# Schemat.net
KiCad netlist of a schematic drawn in Altium Designer
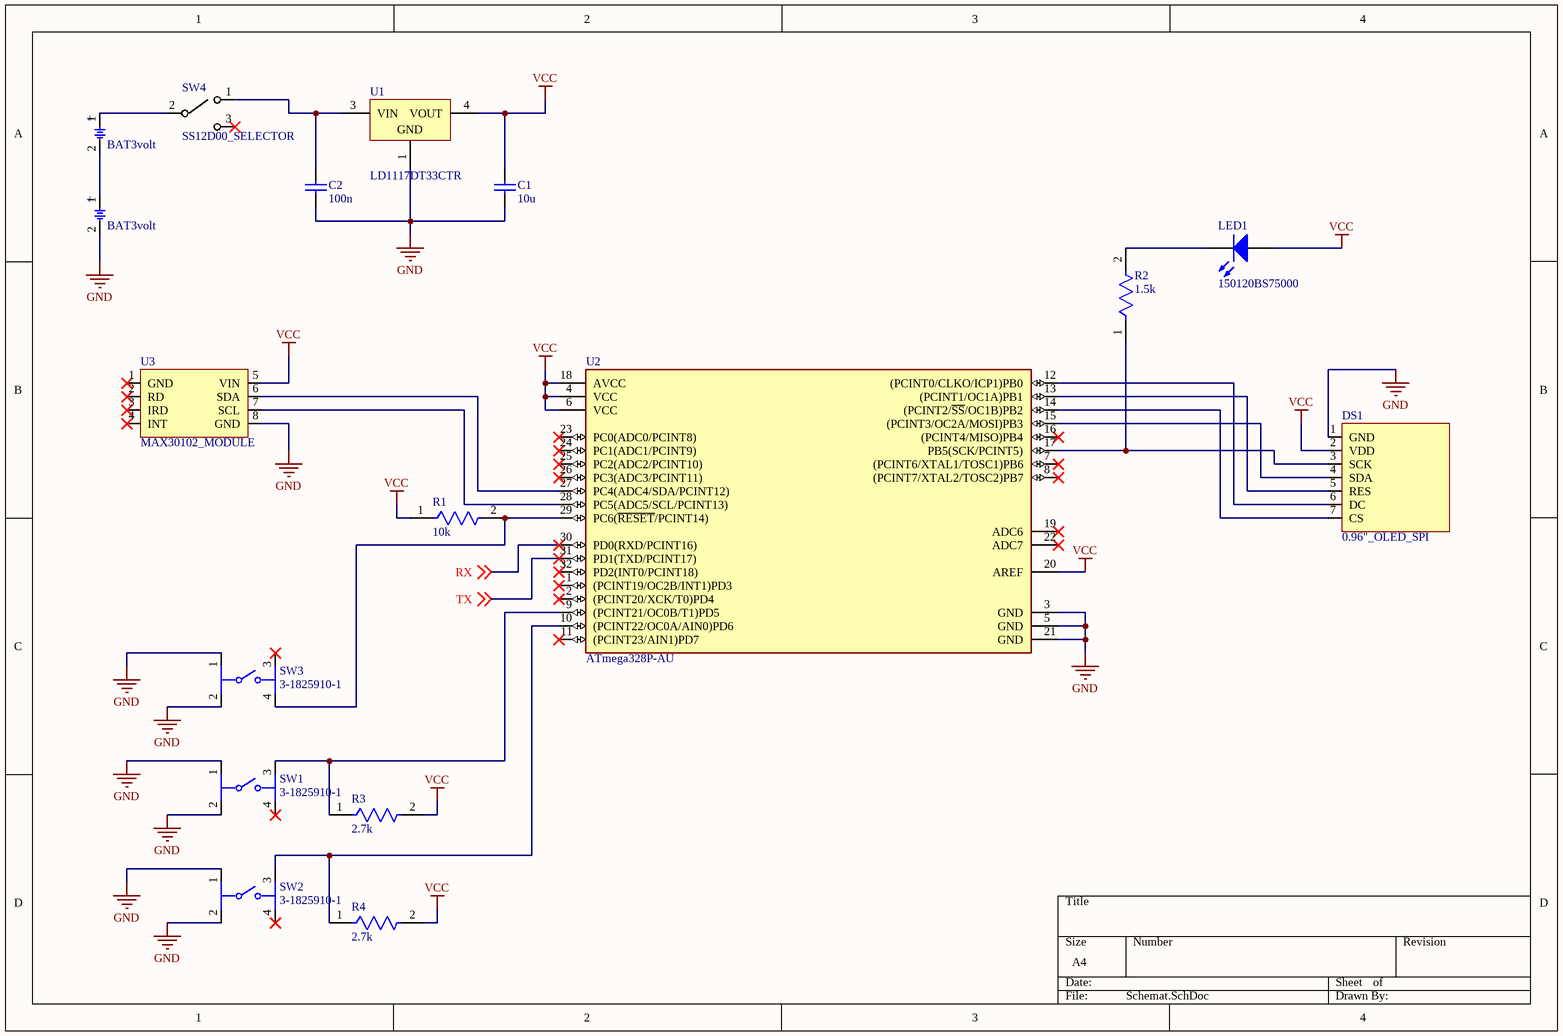
[diagram p0: Schemat.SchDoc]

(export (version "E")
  (design (tool "Eeschema 10.0.6"))
  (components
    (comp (ref "BT1")
      (value "BAT3volt")
      (footprint "BTH2032")
      (description "BATTERY HOLDER, CR2032")
      (libsource (lib "BTH2032") (part "BATH_CR2032"))
    )
    (comp (ref "BT2")
      (value "BAT3volt")
      (footprint "BTH2032")
      (description "BATTERY HOLDER, CR2032")
      (libsource (lib "BTH2032") (part "BATH_CR2032"))
    )
    (comp (ref "C1")
      (value "10u")
      (footprint "CAPC3216X180X50LL20T25")
      (description "Chip Capacitor, 10 uF, +/- 10%, 10 V, -55 to 125 degC, 1206 (3216 Metric), RoHS, Tape and Reel")
      (fields (field (name "TOLERANCE") "10%") (field (name "MANUFACTURER") "Kemet"))
      (libsource (lib "Altium Content Vault") (part "CAP-NP-2"))
    )
    (comp (ref "C2")
      (value "100n")
      (footprint "CAPC3216X94X50ML20T25")
      (description "Chip Capacitor, Ceramic, 100 nF, 10%, 50 V, 1206, RoHS, Tape and Reel")
      (fields (field (name "MANUFACTURER") "AVX"))
      (libsource (lib "Altium Content Vault") (part "CAP-NP-2"))
    )
    (comp (ref "DS1")
      (value "0.96\"_OLED_SPI")
      (footprint "0.96\"_OLED_SPI")
      (description "0.96 inch oled display with SPI interface")
      (libsource (lib "0,96_OLED_SPI") (part "0.96{dblquote}_OLED_SPI"))
    )
    (comp (ref "LED1")
      (value "150120BS75000")
      (footprint "1206_A")
      (description "SMD mono-color Chip LED, WL-SMCW, Blue")
      (fields (field (name "MANUFACTURER") "Wuerth Elektronik"))
      (libsource (lib "Altium Content Vault") (part "WE-LED_K1A2-2"))
    )
    (comp (ref "R1")
      (value "10k")
      (footprint "FP-CRCW1206-e3-IPC_C")
      (description "RES Thick Film, 10kΩ, 1%, 0.25W, 100ppm/°C, 1206")
      (fields (field (name "TOLERANCE") "1%"))
      (libsource (lib "Altium Content Vault") (part "1029c3af85768c4190bb7ad29bc67b5"))
    )
    (comp (ref "R2")
      (value "1.5k")
      (footprint "FP-CRCW1206-e3-IPC_C")
      (description "RES Thick Film, 10kΩ, 1%, 0.25W, 100ppm/°C, 1206")
      (fields (field (name "TOLERANCE") "1%"))
      (libsource (lib "Altium Content Vault") (part "1029c3af85768c4190bb7ad29bc67b5"))
    )
    (comp (ref "R3")
      (value "2.7k")
      (footprint "FP-CRCW1206-e3-IPC_C")
      (description "RES Thick Film, 10kΩ, 1%, 0.25W, 100ppm/°C, 1206")
      (fields (field (name "TOLERANCE") "1%"))
      (libsource (lib "Altium Content Vault") (part "1029c3af85768c4190bb7ad29bc67b5"))
    )
    (comp (ref "R4")
      (value "2.7k")
      (footprint "FP-CRCW1206-e3-IPC_C")
      (description "RES Thick Film, 10kΩ, 1%, 0.25W, 100ppm/°C, 1206")
      (fields (field (name "TOLERANCE") "1%"))
      (libsource (lib "Altium Content Vault") (part "1029c3af85768c4190bb7ad29bc67b5"))
    )
    (comp (ref "SW1")
      (value "3-1825910-1")
      (footprint "FP-3-1825910-1-MFG")
      (description "SWITCH TACTILE SPST-NO 0.05A 24V")
      (fields
        (field (name "MANUFACTURER") "TE Connectivity")
        (field (name "OCTOPART") "https://octopart.com/3-1825910-1-te+connectivity-46506874")
      )
      (libsource (lib "Altium Content Vault") (part "b8895f3f4cefb76e1819d2863dba89b"))
    )
    (comp (ref "SW2")
      (value "3-1825910-1")
      (footprint "FP-3-1825910-1-MFG")
      (description "SWITCH TACTILE SPST-NO 0.05A 24V")
      (fields
        (field (name "MANUFACTURER") "TE Connectivity")
        (field (name "OCTOPART") "https://octopart.com/3-1825910-1-te+connectivity-46506874")
      )
      (libsource (lib "Altium Content Vault") (part "b8895f3f4cefb76e1819d2863dba89b"))
    )
    (comp (ref "SW3")
      (value "3-1825910-1")
      (footprint "FP-3-1825910-1-MFG")
      (description "SWITCH TACTILE SPST-NO 0.05A 24V")
      (fields
        (field (name "MANUFACTURER") "TE Connectivity")
        (field (name "OCTOPART") "https://octopart.com/3-1825910-1-te+connectivity-46506874")
      )
      (libsource (lib "Altium Content Vault") (part "b8895f3f4cefb76e1819d2863dba89b"))
    )
    (comp (ref "SW4")
      (value "SS12D00_SELECTOR")
      (footprint "SS12D00_SELECTOR")
      (description "3.5 x 8.6 mm selector switch")
      (libsource (lib "SS12D00_SELECTOR") (part "SS12D00_SELECTOR"))
    )
    (comp (ref "U1")
      (value "LD1117DT33CTR")
      (footprint "TO-252_N")
      (description "Fixed Low Drop Positive Voltage Regulator, 3.3V, 3-Pin DPAK, Tape and Reel")
      (libsource (lib "Altium Content Vault") (part "PM-REG-LD1117-SOT3"))
    )
    (comp (ref "U2")
      (value "ATmega328P-AU")
      (footprint "FP-32A-MFG")
      (description "IC MCU 8BIT 32KB FLASH 32TQFP")
      (fields
        (field (name "MANUFACTURER") "Microchip")
        (field (name "OCTOPART") "https://octopart.com/atmega328p-au-microchip-77760215")
      )
      (libsource (lib "Altium Content Vault") (part "f5fbdcb2c0c597ef7d3dd1575aef21a"))
    )
    (comp (ref "U3")
      (value "MAX30102_MODULE")
      (footprint "MAX30102_MODULE")
      (description "Arduino module for MAX30102 pulseoxymeter sensor")
      (libsource (lib "MAX30102_MODULE") (part "MAX30102_MODULE"))
    )
  )
  (nets
    (net (code "1") (name "GND") (class "Default")
      (node (ref "BT1") (pin "2") (pinfunction "2_2") (pintype "passive"))
      (node (ref "C1") (pin "1") (pinfunction "1_1") (pintype "passive"))
      (node (ref "C2") (pin "1") (pinfunction "1_1") (pintype "passive"))
      (node (ref "DS1") (pin "1") (pinfunction "GND_1") (pintype "passive"))
      (node (ref "SW1") (pin "1") (pinfunction "1_1") (pintype "passive"))
      (node (ref "SW1") (pin "2") (pinfunction "2_2") (pintype "passive"))
      (node (ref "SW2") (pin "1") (pinfunction "1_1") (pintype "passive"))
      (node (ref "SW2") (pin "2") (pinfunction "2_2") (pintype "passive"))
      (node (ref "SW3") (pin "1") (pinfunction "1_1") (pintype "passive"))
      (node (ref "SW3") (pin "2") (pinfunction "2_2") (pintype "passive"))
      (node (ref "U1") (pin "1") (pinfunction "GND_1") (pintype "power_in"))
      (node (ref "U2") (pin "21") (pinfunction "GND_21") (pintype "power_in"))
      (node (ref "U2") (pin "3") (pinfunction "GND_3") (pintype "power_in"))
      (node (ref "U2") (pin "5") (pinfunction "GND_5") (pintype "power_in"))
      (node (ref "U3") (pin "8") (pinfunction "GND_8") (pintype "passive"))
    )
    (net (code "2") (name "Net-(BT1-Pad1)") (class "Default")
      (node (ref "BT1") (pin "1") (pinfunction "1_1") (pintype "passive"))
      (node (ref "BT2") (pin "2") (pinfunction "2_2") (pintype "passive"))
    )
    (net (code "3") (name "Net-(BT2-Pad1)") (class "Default")
      (node (ref "BT2") (pin "1") (pinfunction "1_1") (pintype "passive"))
      (node (ref "SW4") (pin "2") (pintype "passive"))
    )
    (net (code "4") (name "Net-(DS1-CS)") (class "Default")
      (node (ref "DS1") (pin "7") (pinfunction "CS_7") (pintype "passive"))
      (node (ref "U2") (pin "14") (pinfunction "(PCINT2/~{SS}/OC1B)PB2_14") (pintype "bidirectional"))
    )
    (net (code "5") (name "Net-(DS1-DC)") (class "Default")
      (node (ref "DS1") (pin "6") (pinfunction "DC_6") (pintype "passive"))
      (node (ref "U2") (pin "12") (pinfunction "(PCINT0/CLKO/ICP1)PB0_12") (pintype "bidirectional"))
    )
    (net (code "6") (name "Net-(DS1-RES)") (class "Default")
      (node (ref "DS1") (pin "5") (pinfunction "RES_5") (pintype "passive"))
      (node (ref "U2") (pin "13") (pinfunction "(PCINT1/OC1A)PB1_13") (pintype "bidirectional"))
    )
    (net (code "7") (name "Net-(DS1-SCK)") (class "Default")
      (node (ref "DS1") (pin "3") (pinfunction "SCK_3") (pintype "passive"))
      (node (ref "R2") (pin "1") (pinfunction "1_1") (pintype "passive"))
      (node (ref "U2") (pin "17") (pinfunction "PB5(SCK/PCINT5)_17") (pintype "bidirectional"))
    )
    (net (code "8") (name "Net-(DS1-SDA)") (class "Default")
      (node (ref "DS1") (pin "4") (pinfunction "SDA_4") (pintype "passive"))
      (node (ref "U2") (pin "15") (pinfunction "(PCINT3/OC2A/MOSI)PB3_15") (pintype "bidirectional"))
    )
    (net (code "9") (name "Net-(LED1-K)") (class "Default")
      (node (ref "LED1") (pin "1") (pinfunction "K_1") (pintype "passive"))
      (node (ref "R2") (pin "2") (pinfunction "2_2") (pintype "passive"))
    )
    (net (code "10") (name "Net-(U1-VIN)") (class "Default")
      (node (ref "C2") (pin "2") (pinfunction "2_2") (pintype "passive"))
      (node (ref "SW4") (pin "1") (pintype "passive"))
      (node (ref "U1") (pin "3") (pinfunction "VIN_3") (pintype "power_in"))
    )
    (net (code "11") (name "Net-(U2-(PCINT21{slash}OC0B{slash}T1)PD5)") (class "Default")
      (node (ref "R3") (pin "1") (pinfunction "1_1") (pintype "passive"))
      (node (ref "SW1") (pin "3") (pinfunction "3_3") (pintype "passive"))
      (node (ref "U2") (pin "9") (pinfunction "(PCINT21/OC0B/T1)PD5_9") (pintype "bidirectional"))
    )
    (net (code "12") (name "Net-(U2-(PCINT22{slash}OC0A{slash}AIN0)PD6)") (class "Default")
      (node (ref "R4") (pin "1") (pinfunction "1_1") (pintype "passive"))
      (node (ref "SW2") (pin "3") (pinfunction "3_3") (pintype "passive"))
      (node (ref "U2") (pin "10") (pinfunction "(PCINT22/OC0A/AIN0)PD6_10") (pintype "bidirectional"))
    )
    (net (code "13") (name "Net-(U2-PC4(ADC4{slash}SDA{slash}PCINT12))") (class "Default")
      (node (ref "U2") (pin "27") (pinfunction "PC4(ADC4/SDA/PCINT12)_27") (pintype "bidirectional"))
      (node (ref "U3") (pin "6") (pinfunction "SDA_6") (pintype "passive"))
    )
    (net (code "14") (name "Net-(U2-PC5(ADC5{slash}SCL{slash}PCINT13))") (class "Default")
      (node (ref "U2") (pin "28") (pinfunction "PC5(ADC5/SCL/PCINT13)_28") (pintype "bidirectional"))
      (node (ref "U3") (pin "7") (pinfunction "SCL_7") (pintype "passive"))
    )
    (net (code "15") (name "Net-(U2-PC6(~{RESET}{slash}PCINT14))") (class "Default")
      (node (ref "R1") (pin "2") (pinfunction "2_2") (pintype "passive"))
      (node (ref "SW3") (pin "4") (pinfunction "4_4") (pintype "passive"))
      (node (ref "U2") (pin "29") (pinfunction "PC6(~{RESET}/PCINT14)_29") (pintype "bidirectional"))
    )
    (net (code "16") (name "RX") (class "Default")
      (node (ref "U2") (pin "30") (pinfunction "PD0(RXD/PCINT16)_30") (pintype "bidirectional"))
    )
    (net (code "17") (name "TX") (class "Default")
      (node (ref "U2") (pin "31") (pinfunction "PD1(TXD/PCINT17)_31") (pintype "bidirectional"))
    )
    (net (code "18") (name "VCC") (class "Default")
      (node (ref "C1") (pin "2") (pinfunction "2_2") (pintype "passive"))
      (node (ref "DS1") (pin "2") (pinfunction "VDD_2") (pintype "passive"))
      (node (ref "LED1") (pin "2") (pinfunction "A_2") (pintype "passive"))
      (node (ref "R1") (pin "1") (pinfunction "1_1") (pintype "passive"))
      (node (ref "R3") (pin "2") (pinfunction "2_2") (pintype "passive"))
      (node (ref "R4") (pin "2") (pinfunction "2_2") (pintype "passive"))
      (node (ref "U1") (pin "4") (pinfunction "VOUT_4") (pintype "power_in"))
      (node (ref "U2") (pin "18") (pinfunction "AVCC_18") (pintype "power_in"))
      (node (ref "U2") (pin "20") (pinfunction "AREF_20") (pintype "passive"))
      (node (ref "U2") (pin "4") (pinfunction "VCC_4") (pintype "power_in"))
      (node (ref "U2") (pin "6") (pinfunction "VCC_6") (pintype "power_in"))
      (node (ref "U3") (pin "5") (pinfunction "VIN_5") (pintype "passive"))
    )
    (net (code "19") (name "unconnected-(SW1-Pad4)") (class "Default")
      (node (ref "SW1") (pin "4") (pinfunction "4_4") (pintype "passive+no_connect"))
    )
    (net (code "20") (name "unconnected-(SW2-Pad4)") (class "Default")
      (node (ref "SW2") (pin "4") (pinfunction "4_4") (pintype "passive+no_connect"))
    )
    (net (code "21") (name "unconnected-(SW3-Pad3)") (class "Default")
      (node (ref "SW3") (pin "3") (pinfunction "3_3") (pintype "passive+no_connect"))
    )
    (net (code "22") (name "unconnected-(SW4-Pad3)") (class "Default")
      (node (ref "SW4") (pin "3") (pintype "passive+no_connect"))
    )
    (net (code "23") (name "unconnected-(U2-(PCINT4{slash}MISO)PB4-Pad16)") (class "Default")
      (node (ref "U2") (pin "16") (pinfunction "(PCINT4/MISO)PB4_16") (pintype "bidirectional+no_connect"))
    )
    (net (code "24") (name "unconnected-(U2-(PCINT6{slash}XTAL1{slash}TOSC1)PB6-Pad7)") (class "Default")
      (node (ref "U2") (pin "7") (pinfunction "(PCINT6/XTAL1/TOSC1)PB6_7") (pintype "bidirectional+no_connect"))
    )
    (net (code "25") (name "unconnected-(U2-(PCINT7{slash}XTAL2{slash}TOSC2)PB7-Pad8)") (class "Default")
      (node (ref "U2") (pin "8") (pinfunction "(PCINT7/XTAL2/TOSC2)PB7_8") (pintype "bidirectional+no_connect"))
    )
    (net (code "26") (name "unconnected-(U2-(PCINT19{slash}OC2B{slash}INT1)PD3-Pad1)") (class "Default")
      (node (ref "U2") (pin "1") (pinfunction "(PCINT19/OC2B/INT1)PD3_1") (pintype "bidirectional+no_connect"))
    )
    (net (code "27") (name "unconnected-(U2-(PCINT20{slash}XCK{slash}T0)PD4-Pad2)") (class "Default")
      (node (ref "U2") (pin "2") (pinfunction "(PCINT20/XCK/T0)PD4_2") (pintype "bidirectional+no_connect"))
    )
    (net (code "28") (name "unconnected-(U2-(PCINT23{slash}AIN1)PD7-Pad11)") (class "Default")
      (node (ref "U2") (pin "11") (pinfunction "(PCINT23/AIN1)PD7_11") (pintype "bidirectional+no_connect"))
    )
    (net (code "29") (name "unconnected-(U2-ADC6-Pad19)") (class "Default")
      (node (ref "U2") (pin "19") (pinfunction "ADC6_19") (pintype "power_in+no_connect"))
    )
    (net (code "30") (name "unconnected-(U2-ADC7-Pad22)") (class "Default")
      (node (ref "U2") (pin "22") (pinfunction "ADC7_22") (pintype "passive+no_connect"))
    )
    (net (code "31") (name "unconnected-(U2-PC0(ADC0{slash}PCINT8)-Pad23)") (class "Default")
      (node (ref "U2") (pin "23") (pinfunction "PC0(ADC0/PCINT8)_23") (pintype "bidirectional+no_connect"))
    )
    (net (code "32") (name "unconnected-(U2-PC1(ADC1{slash}PCINT9)-Pad24)") (class "Default")
      (node (ref "U2") (pin "24") (pinfunction "PC1(ADC1/PCINT9)_24") (pintype "bidirectional+no_connect"))
    )
    (net (code "33") (name "unconnected-(U2-PC2(ADC2{slash}PCINT10)-Pad25)") (class "Default")
      (node (ref "U2") (pin "25") (pinfunction "PC2(ADC2/PCINT10)_25") (pintype "bidirectional+no_connect"))
    )
    (net (code "34") (name "unconnected-(U2-PC3(ADC3{slash}PCINT11)-Pad26)") (class "Default")
      (node (ref "U2") (pin "26") (pinfunction "PC3(ADC3/PCINT11)_26") (pintype "bidirectional+no_connect"))
    )
    (net (code "35") (name "unconnected-(U2-PD2(INT0{slash}PCINT18)-Pad32)") (class "Default")
      (node (ref "U2") (pin "32") (pinfunction "PD2(INT0/PCINT18)_32") (pintype "bidirectional+no_connect"))
    )
    (net (code "36") (name "unconnected-(U3-GND-Pad1)") (class "Default")
      (node (ref "U3") (pin "1") (pinfunction "GND_1") (pintype "passive+no_connect"))
    )
    (net (code "37") (name "unconnected-(U3-INT-Pad4)") (class "Default")
      (node (ref "U3") (pin "4") (pinfunction "INT_4") (pintype "passive+no_connect"))
    )
    (net (code "38") (name "unconnected-(U3-IRD-Pad3)") (class "Default")
      (node (ref "U3") (pin "3") (pinfunction "IRD_3") (pintype "passive+no_connect"))
    )
    (net (code "39") (name "unconnected-(U3-RD-Pad2)") (class "Default")
      (node (ref "U3") (pin "2") (pinfunction "RD_2") (pintype "passive+no_connect"))
    )
  )
)
